# Sheet1.net
KiCad netlist of a schematic drawn in Altium Designer
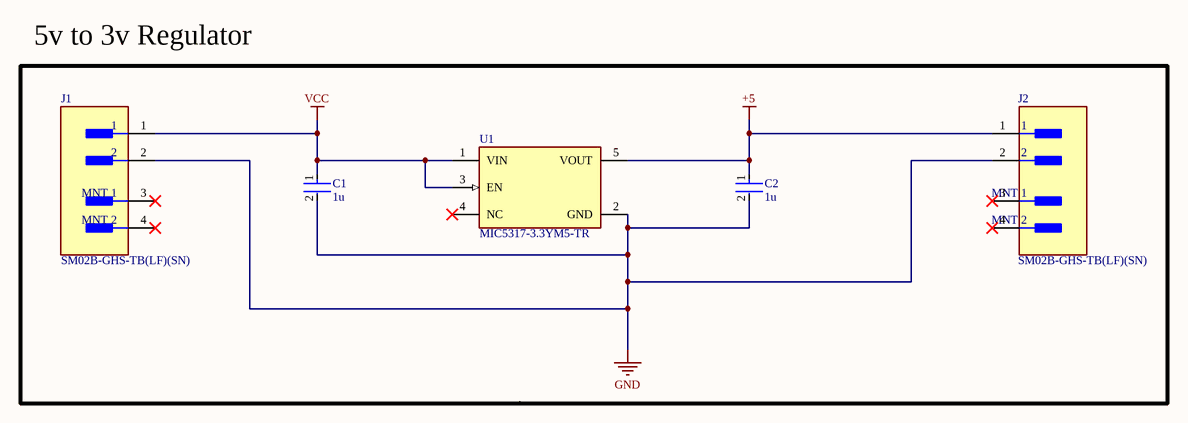
[diagram p0: Sheet1.SchDoc]

(export (version "E")
  (design (tool "Eeschema 10.0.6"))
  (components
    (comp (ref "C1")
      (value "1u")
      (footprint "FP-CC0805-0_2-1_45-IPC_A")
      (description "CAP CER 10UF 10V X5R 0805")
      (fields (field (name "VOLTAGE") "10V") (field (name "TOLERANCE") "10%"))
      (libsource (lib "Altium Content Vault") (part "e9c51b7dd13d4faca003ae77663ab08"))
    )
    (comp (ref "C2")
      (value "1u")
      (footprint "FP-CC0805-0_2-1_45-IPC_A")
      (description "CAP CER 10UF 10V X5R 0805")
      (fields (field (name "VOLTAGE") "10V") (field (name "TOLERANCE") "10%"))
      (libsource (lib "Altium Content Vault") (part "e9c51b7dd13d4faca003ae77663ab08"))
    )
    (comp (ref "J1")
      (value "SM02B-GHS-TB(LF)(SN)")
      (footprint "FP-SM02B-GHS-TB_LF_SN-MFG")
      (description "CONN HEADER SMD R/A 2POS 1.25MM")
      (libsource (lib "Altium Content Vault") (part "56ec3178a87b3978bdc1b3682cd516a"))
    )
    (comp (ref "J2")
      (value "SM02B-GHS-TB(LF)(SN)")
      (footprint "FP-SM02B-GHS-TB_LF_SN-MFG")
      (description "CONN HEADER SMD R/A 2POS 1.25MM")
      (libsource (lib "") (part "56ec3178a87b3978bdc1b3682cd516a_1"))
    )
    (comp (ref "U1")
      (value "MIC5317-3.3YM5-TR")
      (footprint "FP-SOT23-5LD-PL-1-MFG")
      (description "IC REG LINEAR 3.3V 150MA SOT23-5")
      (libsource (lib "Altium Content Vault") (part "0a093dae7315cdc977fd108dde87457"))
    )
  )
  (nets
    (net (code "1") (name "+5") (class "Default")
      (node (ref "C2") (pin "1") (pinfunction "1_1") (pintype "passive"))
      (node (ref "J2") (pin "1") (pinfunction "1_1") (pintype "passive"))
      (node (ref "U1") (pin "5") (pinfunction "VOUT_5") (pintype "power_in"))
    )
    (net (code "2") (name "GND") (class "Default")
      (node (ref "C1") (pin "2") (pinfunction "2_2") (pintype "passive"))
      (node (ref "C2") (pin "2") (pinfunction "2_2") (pintype "passive"))
      (node (ref "J1") (pin "2") (pinfunction "2_2") (pintype "passive"))
      (node (ref "J2") (pin "2") (pinfunction "2_2") (pintype "passive"))
      (node (ref "U1") (pin "2") (pinfunction "GND_2") (pintype "power_in"))
    )
    (net (code "3") (name "VCC") (class "Default")
      (node (ref "C1") (pin "1") (pinfunction "1_1") (pintype "passive"))
      (node (ref "J1") (pin "1") (pinfunction "1_1") (pintype "passive"))
      (node (ref "U1") (pin "1") (pinfunction "VIN_1") (pintype "power_in"))
      (node (ref "U1") (pin "3") (pinfunction "EN_3") (pintype "input"))
    )
    (net (code "4") (name "unconnected-(J1-MNT_1-Pad3)") (class "Default")
      (node (ref "J1") (pin "3") (pinfunction "MNT_1_3") (pintype "passive+no_connect"))
    )
    (net (code "5") (name "unconnected-(J1-MNT_2-Pad4)") (class "Default")
      (node (ref "J1") (pin "4") (pinfunction "MNT_2_4") (pintype "passive+no_connect"))
    )
    (net (code "6") (name "unconnected-(J2-MNT_1-Pad3)") (class "Default")
      (node (ref "J2") (pin "3") (pinfunction "MNT_1_3") (pintype "passive+no_connect"))
    )
    (net (code "7") (name "unconnected-(J2-MNT_2-Pad4)") (class "Default")
      (node (ref "J2") (pin "4") (pinfunction "MNT_2_4") (pintype "passive+no_connect"))
    )
    (net (code "8") (name "unconnected-(U1-NC-Pad4)") (class "Default")
      (node (ref "U1") (pin "4") (pinfunction "NC_4") (pintype "passive+no_connect"))
    )
  )
)
